# rapidshark-clip-detector-mk-1_2a.net
KiCad netlist of a schematic drawn in EAGLE
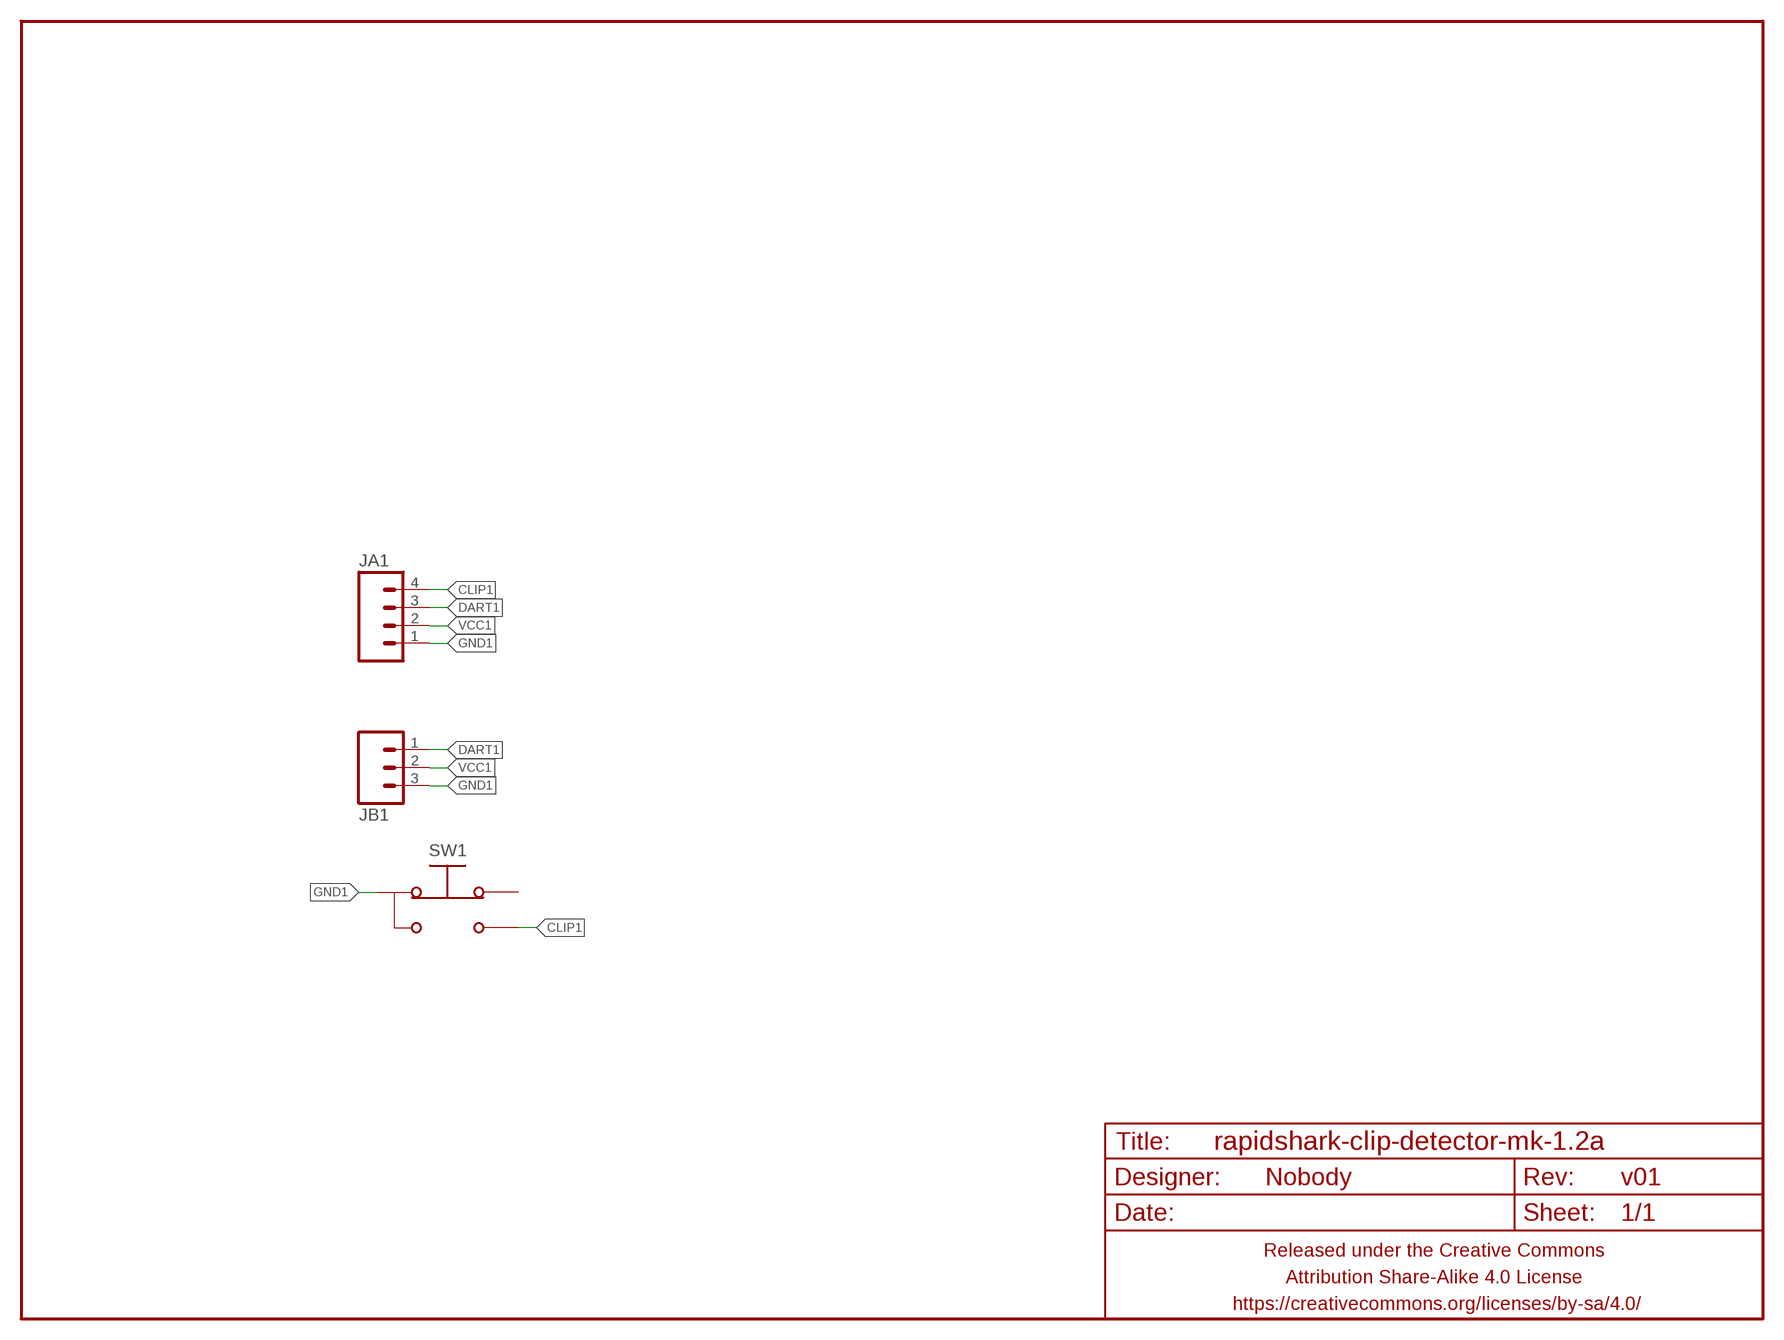
[diagram p0: schematic, sheet 1]

(export (version "E")
  (design (tool "Eeschema 10.0.6"))
  (components
    (comp (ref "FRAME1")
      (value "FRAME-LETTERNO_PACKAGE")
      (footprint "eagle-import:DUMMY")
      (fields (field (name "DESIGNER") "Nobody"))
      (libsource (lib "eagle-import") (part "FRAME-LETTERNO_PACKAGE"))
    )
    (comp (ref "JA1")
      (value "M04JST-PTH-VERT")
      (footprint "eagle-import:JST-4-PH-VERT-PTH")
      (libsource (lib "eagle-import") (part "M04JST-PTH-VERT"))
    )
    (comp (ref "JB1")
      (value "M03JST-PTH-VERT")
      (footprint "eagle-import:JST-3-PH-VERT-PTH")
      (libsource (lib "eagle-import") (part "M03JST-PTH-VERT"))
    )
    (comp (ref "SW1")
      (value "SPDT-NO-TACTPTH-RA-DETECT-3MM")
      (footprint "eagle-import:SWITCH-DETECH-SPDT-3MM")
      (libsource (lib "eagle-import") (part "SPDT-NO-TACTPTH-RA-DETECT-3MM"))
    )
  )
  (nets
    (net (code "1") (name "CLIP1") (class "Default")
      (node (ref "JA1") (pin "4") (pinfunction "4_4") (pintype "passive"))
      (node (ref "SW1") (pin "3") (pinfunction "NO_3") (pintype "bidirectional"))
    )
    (net (code "2") (name "DART1") (class "Default")
      (node (ref "JA1") (pin "3") (pinfunction "3_3") (pintype "passive"))
      (node (ref "JB1") (pin "1") (pinfunction "1_1") (pintype "passive"))
    )
    (net (code "3") (name "GND1") (class "Default")
      (node (ref "JA1") (pin "1") (pinfunction "1_1") (pintype "passive"))
      (node (ref "JB1") (pin "3") (pinfunction "3_3") (pintype "passive"))
      (node (ref "SW1") (pin "2") (pinfunction "COM_2") (pintype "bidirectional"))
    )
    (net (code "4") (name "VCC1") (class "Default")
      (node (ref "JA1") (pin "2") (pinfunction "2_2") (pintype "passive"))
      (node (ref "JB1") (pin "2") (pinfunction "2_2") (pintype "passive"))
    )
    (net (code "5") (name "unconnected-(SW1-NC-Pad1)") (class "Default")
      (node (ref "SW1") (pin "1") (pinfunction "NC_1") (pintype "bidirectional"))
    )
  )
)
